# design.net
KiCad netlist of a schematic drawn in Altium Designer
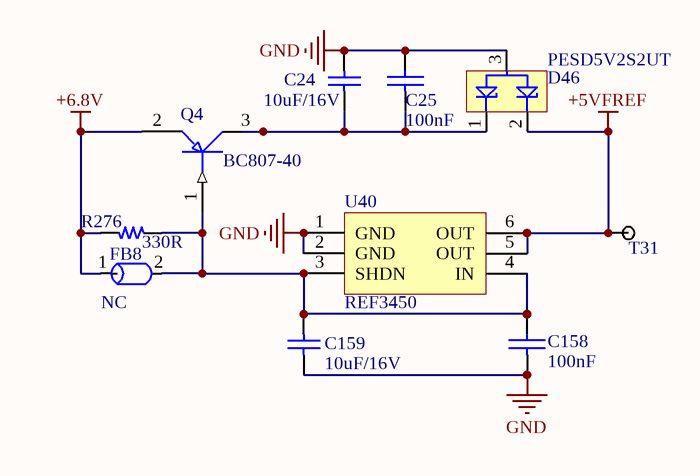
[diagram p0: 基准.SchDoc]

(export (version "E")
  (design (tool "Eeschema 10.0.6"))
  (components
    (comp (ref "C24")
      (value "10uF/16V")
      (footprint "C-0805")
      (description "贴片瓷介电容100nF±5%,0805")
      (libsource (lib "电容") (part "100nF_1"))
    )
    (comp (ref "C25")
      (value "100nF")
      (footprint "C-0603")
      (description "Capacitor")
      (libsource (lib "*") (part "CAP"))
    )
    (comp (ref "C158")
      (value "100nF")
      (footprint "C-0603")
      (description "Capacitor")
      (libsource (lib "*") (part "CAP"))
    )
    (comp (ref "C159")
      (value "10uF/16V")
      (footprint "C-0805")
      (description "贴片瓷介电容100nF±5%,0805")
      (libsource (lib "电容") (part "100nF_1"))
    )
    (comp (ref "D46") (value "PESD5V2S2UT") (footprint "sot23-3") (libsource (lib "IC") (part "PESDxS2UT")))
    (comp (ref "FB8")
      (value "NC")
      (footprint "R-0805")
      (description "Rdc0.3Ω,伍尔特,742792032")
      (libsource (lib "其它") (part "FB_1K/500mA_0805"))
    )
    (comp (ref "Q4") (value "BC807-40") (footprint "SOT23-3") (libsource (lib "NBP电源板封装") (part "BC807-40")))
    (comp (ref "R276")
      (value "330R")
      (footprint "R-0805")
      (description "国巨RC0805FR-07100R")
      (libsource (lib "电阻") (part "100Ω_1"))
    )
    (comp (ref "T31") (value "直插测试点") (footprint "DIPTP") (libsource (lib "其它") (part "Testpiont")))
    (comp (ref "U40") (value "REF3450") (footprint "SOT23-6") (libsource (lib "*") (part "REF3225")))
  )
  (nets
    (net (code "1") (name "+5VFREF") (class "Default")
      (node (ref "D46") (pin "2") (pinfunction "2_2") (pintype "passive"))
      (node (ref "T31") (pin "1") (pinfunction "1_1") (pintype "passive"))
      (node (ref "U40") (pin "5") (pinfunction "OUT_5") (pintype "passive"))
      (node (ref "U40") (pin "6") (pinfunction "OUT_6") (pintype "passive"))
    )
    (net (code "2") (name "+6.8V") (class "Default")
      (node (ref "FB8") (pin "1") (pinfunction "1_1") (pintype "passive"))
      (node (ref "Q4") (pin "2") (pinfunction "E_2") (pintype "passive"))
      (node (ref "R276") (pin "2") (pinfunction "BOT_2") (pintype "passive"))
    )
    (net (code "3") (name "GND") (class "Default")
      (node (ref "C158") (pin "1") (pinfunction "1_1") (pintype "passive"))
      (node (ref "C159") (pin "1") (pinfunction "1_1") (pintype "passive"))
      (node (ref "C24") (pin "2") (pinfunction "2_2") (pintype "passive"))
      (node (ref "C25") (pin "2") (pinfunction "2_2") (pintype "passive"))
      (node (ref "D46") (pin "3") (pinfunction "3_3") (pintype "passive"))
      (node (ref "U40") (pin "1") (pinfunction "GND_1") (pintype "passive"))
      (node (ref "U40") (pin "2") (pinfunction "GND_2") (pintype "passive"))
    )
    (net (code "4") (name "Net-(Q4-B)") (class "Default")
      (node (ref "C158") (pin "2") (pinfunction "2_2") (pintype "passive"))
      (node (ref "C159") (pin "2") (pinfunction "2_2") (pintype "passive"))
      (node (ref "FB8") (pin "2") (pinfunction "2_2") (pintype "passive"))
      (node (ref "Q4") (pin "1") (pinfunction "B_1") (pintype "input"))
      (node (ref "R276") (pin "1") (pinfunction "TOP_1") (pintype "passive"))
      (node (ref "U40") (pin "3") (pinfunction "SHDN_3") (pintype "passive"))
      (node (ref "U40") (pin "4") (pinfunction "IN_4") (pintype "passive"))
    )
    (net (code "5") (name "Net-(Q4-C)") (class "Default")
      (node (ref "C24") (pin "1") (pinfunction "1_1") (pintype "passive"))
      (node (ref "C25") (pin "1") (pinfunction "1_1") (pintype "passive"))
      (node (ref "D46") (pin "1") (pinfunction "1_1") (pintype "passive"))
      (node (ref "Q4") (pin "3") (pinfunction "C_3") (pintype "passive"))
    )
  )
)
